# Atemgea_schematic.net
KiCad netlist of a schematic drawn in Altium Designer
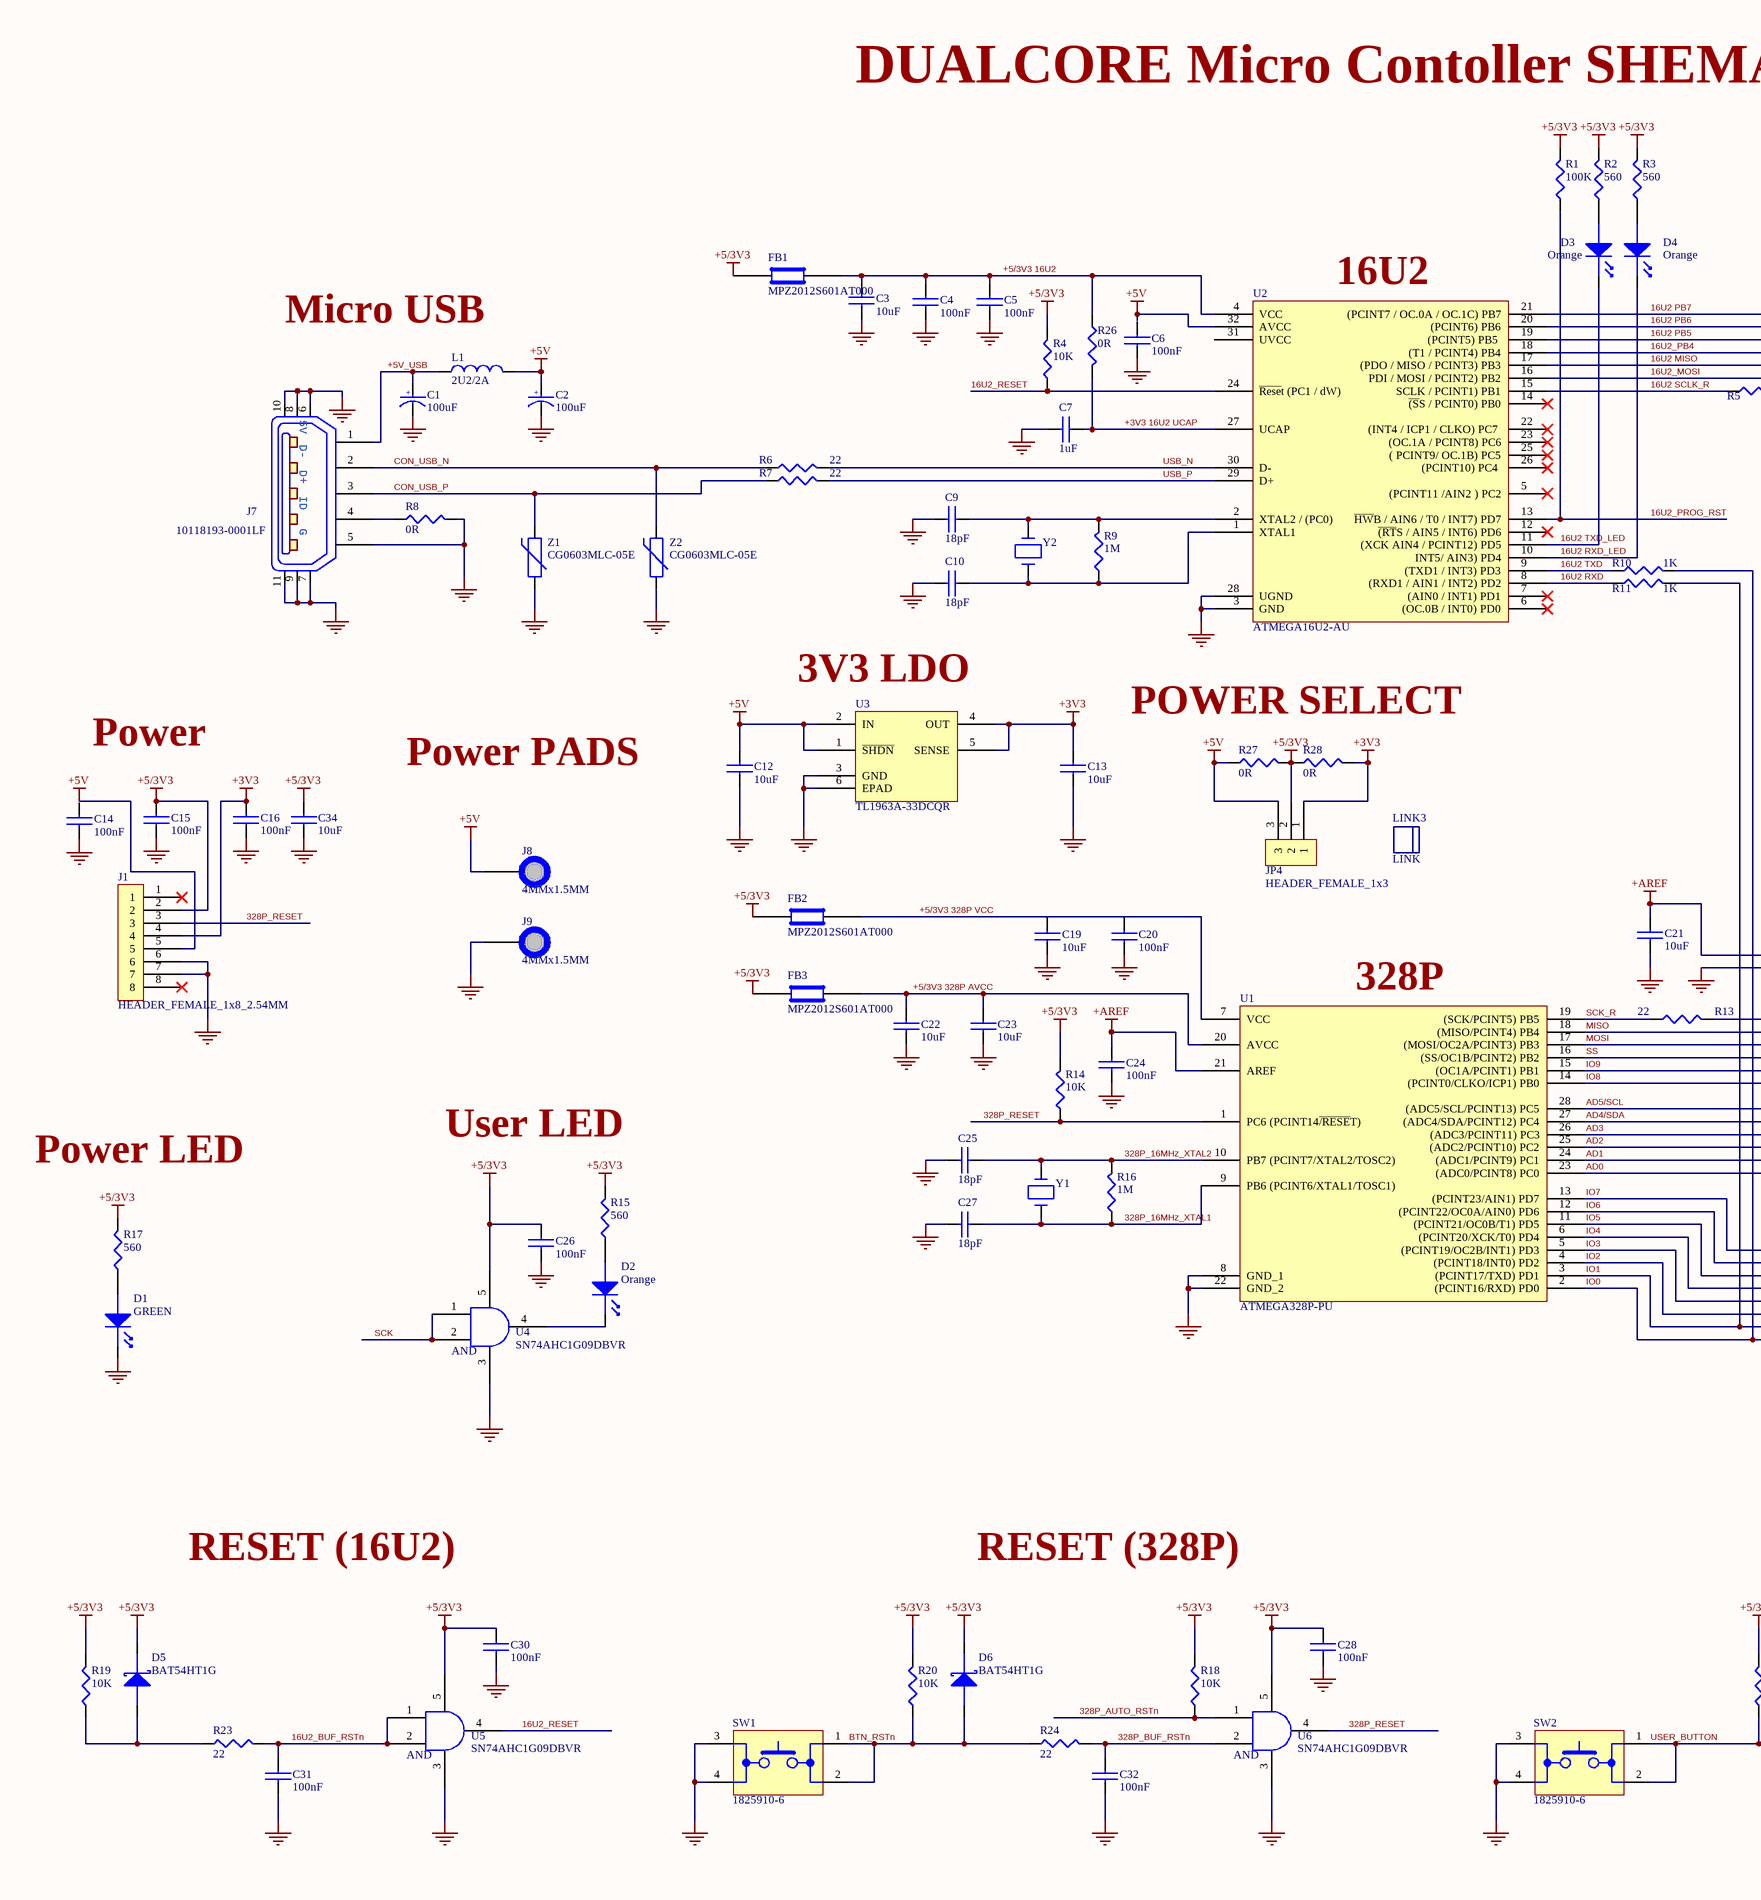
[diagram p0: Atemgea_schematic.SchDoc, left]
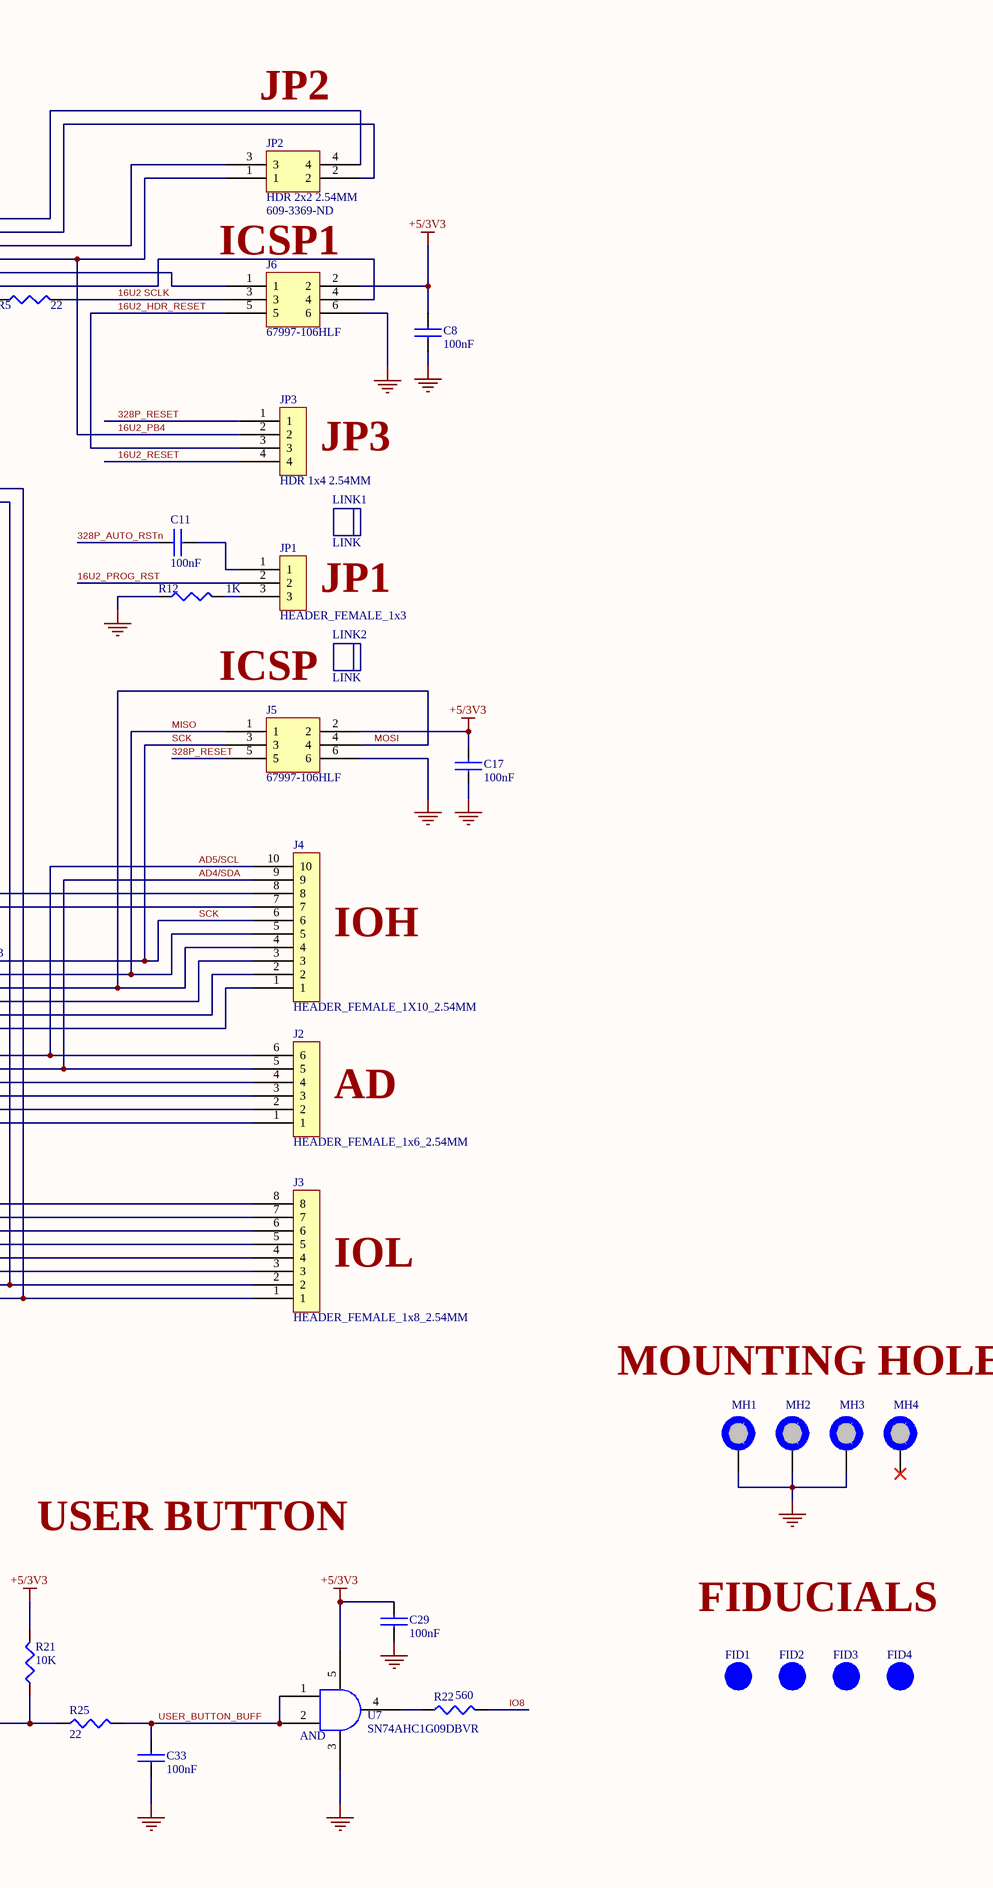
[diagram p1: Atemgea_schematic.SchDoc, right]

(export (version "E")
  (design (tool "Eeschema 10.0.6"))
  (components
    (comp (ref "C1")
      (value "100uF")
      (footprint "C_ALU_C_SIZE")
      (description "Cap Aluminum 100uF 10V 20% (5 X 5.4mm) SMD 50mA 1000 hr 85°C T/R")
      (fields
        (field (name "MANUFACTURER") "Panasonic")
        (field (name "MANUFACTURER PART NUMBER") "EEE-1AA101WR")
      )
      (libsource (lib "atmega_shlib") (part "EEE-1AA101WR"))
    )
    (comp (ref "C2")
      (value "100uF")
      (footprint "C_ALU_C_SIZE")
      (description "Cap Aluminum 100uF 10V 20% (5 X 5.4mm) SMD 50mA 1000 hr 85°C T/R")
      (fields
        (field (name "MANUFACTURER") "Panasonic")
        (field (name "MANUFACTURER PART NUMBER") "EEE-1AA101WR")
      )
      (libsource (lib "atmega_shlib") (part "EEE-1AA101WR"))
    )
    (comp (ref "C3")
      (value "10uF")
      (footprint "C0805")
      (description "Cap Ceramic 10uF 10V X7S 20% Pad SMD 0805 125°C Low ESR Automotive T/R")
      (fields
        (field (name "MANUFACTURER") "TDK")
        (field (name "MANUFACTURER PART NUMBER") "CGA4J3X7S1A106M125AB")
      )
      (libsource (lib "atmega_shlib") (part "CGA4J3X7S1A106M125AB"))
    )
    (comp (ref "C4")
      (value "100nF")
      (footprint "C0805")
      (description "Cap Ceramic 0.1uF 50V X7R 10% Pad SMD 0805 125°C Automotive T/R")
      (fields
        (field (name "MANUFACTURER") "TDK")
        (field (name "MANUFACTURER PART NUMBER") "CGA4J2X7R1H104K125AM")
      )
      (libsource (lib "atmega_shlib") (part "CGA4J2X7R1H104K125AM"))
    )
    (comp (ref "C5")
      (value "100nF")
      (footprint "C0805")
      (description "Cap Ceramic 0.1uF 50V X7R 10% Pad SMD 0805 125°C Automotive T/R")
      (fields
        (field (name "MANUFACTURER") "TDK")
        (field (name "MANUFACTURER PART NUMBER") "CGA4J2X7R1H104K125AM")
      )
      (libsource (lib "atmega_shlib") (part "CGA4J2X7R1H104K125AM"))
    )
    (comp (ref "C6")
      (value "100nF")
      (footprint "C0805")
      (description "Cap Ceramic 0.1uF 50V X7R 10% Pad SMD 0805 125°C Automotive T/R")
      (fields
        (field (name "MANUFACTURER") "TDK")
        (field (name "MANUFACTURER PART NUMBER") "CGA4J2X7R1H104K125AM")
      )
      (libsource (lib "atmega_shlib") (part "CGA4J2X7R1H104K125AM"))
    )
    (comp (ref "C7")
      (value "1uF")
      (footprint "C0805")
      (fields
        (field (name "MANUFACTURER") "TDK")
        (field (name "MANUFACTURER PART NUMBER") "C2012X5R1E105K125AA")
        (field (name "TOLERANCE") "10%")
      )
      (libsource (lib "atmega_shlib") (part "C2012X5R1E105K125AA"))
    )
    (comp (ref "C8")
      (value "100nF")
      (footprint "C0805")
      (description "Cap Ceramic 0.1uF 50V X7R 10% Pad SMD 0805 125°C Automotive T/R")
      (fields
        (field (name "MANUFACTURER") "TDK")
        (field (name "MANUFACTURER PART NUMBER") "CGA4J2X7R1H104K125AM")
      )
      (libsource (lib "atmega_shlib") (part "CGA4J2X7R1H104K125AM"))
    )
    (comp (ref "C9")
      (value "18pF")
      (footprint "C0805")
      (description "Cap Ceramic 18pF 50V C0G 5% SMD 0805 125C Paper T/R")
      (fields
        (field (name "MANUFACTURER") "KEMET")
        (field (name "MANUFACTURER PART NUMBER") "C0805C180J5GACTU")
      )
      (libsource (lib "atmega_shlib") (part "C0805C180J5GACTU"))
    )
    (comp (ref "C10")
      (value "18pF")
      (footprint "C0805")
      (description "Cap Ceramic 18pF 50V C0G 5% SMD 0805 125C Paper T/R")
      (fields
        (field (name "MANUFACTURER") "KEMET")
        (field (name "MANUFACTURER PART NUMBER") "C0805C180J5GACTU")
      )
      (libsource (lib "atmega_shlib") (part "C0805C180J5GACTU"))
    )
    (comp (ref "C11")
      (value "100nF")
      (footprint "C0805")
      (description "Cap Ceramic 0.1uF 50V X7R 10% Pad SMD 0805 125°C Automotive T/R")
      (fields
        (field (name "MANUFACTURER") "TDK")
        (field (name "MANUFACTURER PART NUMBER") "CGA4J2X7R1H104K125AM")
      )
      (libsource (lib "atmega_shlib") (part "CGA4J2X7R1H104K125AM"))
    )
    (comp (ref "C12")
      (value "10uF")
      (footprint "C0805")
      (description "Cap Ceramic 10uF 10V X7S 20% Pad SMD 0805 125°C Low ESR Automotive T/R")
      (fields
        (field (name "MANUFACTURER") "TDK")
        (field (name "MANUFACTURER PART NUMBER") "CGA4J3X7S1A106M125AB")
      )
      (libsource (lib "atmega_shlib") (part "CGA4J3X7S1A106M125AB"))
    )
    (comp (ref "C13")
      (value "10uF")
      (footprint "C0805")
      (description "Cap Ceramic 10uF 10V X7S 20% Pad SMD 0805 125°C Low ESR Automotive T/R")
      (fields
        (field (name "MANUFACTURER") "TDK")
        (field (name "MANUFACTURER PART NUMBER") "CGA4J3X7S1A106M125AB")
      )
      (libsource (lib "atmega_shlib") (part "CGA4J3X7S1A106M125AB"))
    )
    (comp (ref "C14")
      (value "100nF")
      (footprint "C0805")
      (description "Cap Ceramic 0.1uF 50V X7R 10% Pad SMD 0805 125°C Automotive T/R")
      (fields
        (field (name "MANUFACTURER") "TDK")
        (field (name "MANUFACTURER PART NUMBER") "CGA4J2X7R1H104K125AM")
      )
      (libsource (lib "atmega_shlib") (part "CGA4J2X7R1H104K125AM"))
    )
    (comp (ref "C15")
      (value "100nF")
      (footprint "C0805")
      (description "Cap Ceramic 0.1uF 50V X7R 10% Pad SMD 0805 125°C Automotive T/R")
      (fields
        (field (name "MANUFACTURER") "TDK")
        (field (name "MANUFACTURER PART NUMBER") "CGA4J2X7R1H104K125AM")
      )
      (libsource (lib "atmega_shlib") (part "CGA4J2X7R1H104K125AM"))
    )
    (comp (ref "C16")
      (value "100nF")
      (footprint "C0805")
      (description "Cap Ceramic 0.1uF 50V X7R 10% Pad SMD 0805 125°C Automotive T/R")
      (fields
        (field (name "MANUFACTURER") "TDK")
        (field (name "MANUFACTURER PART NUMBER") "CGA4J2X7R1H104K125AM")
      )
      (libsource (lib "atmega_shlib") (part "CGA4J2X7R1H104K125AM"))
    )
    (comp (ref "C17")
      (value "100nF")
      (footprint "C0805")
      (description "Cap Ceramic 0.1uF 50V X7R 10% Pad SMD 0805 125°C Automotive T/R")
      (fields
        (field (name "MANUFACTURER") "TDK")
        (field (name "MANUFACTURER PART NUMBER") "CGA4J2X7R1H104K125AM")
      )
      (libsource (lib "atmega_shlib") (part "CGA4J2X7R1H104K125AM"))
    )
    (comp (ref "C19")
      (value "10uF")
      (footprint "C0805")
      (description "Cap Ceramic 10uF 10V X7S 20% Pad SMD 0805 125°C Low ESR Automotive T/R")
      (fields
        (field (name "MANUFACTURER") "TDK")
        (field (name "MANUFACTURER PART NUMBER") "CGA4J3X7S1A106M125AB")
      )
      (libsource (lib "atmega_shlib") (part "CGA4J3X7S1A106M125AB"))
    )
    (comp (ref "C20")
      (value "100nF")
      (footprint "C0805")
      (description "Cap Ceramic 0.1uF 50V X7R 10% Pad SMD 0805 125°C Automotive T/R")
      (fields
        (field (name "MANUFACTURER") "TDK")
        (field (name "MANUFACTURER PART NUMBER") "CGA4J2X7R1H104K125AM")
      )
      (libsource (lib "atmega_shlib") (part "CGA4J2X7R1H104K125AM"))
    )
    (comp (ref "C21")
      (value "10uF")
      (footprint "C0805")
      (description "Cap Ceramic 10uF 10V X7S 20% Pad SMD 0805 125°C Low ESR Automotive T/R")
      (fields
        (field (name "MANUFACTURER") "TDK")
        (field (name "MANUFACTURER PART NUMBER") "CGA4J3X7S1A106M125AB")
      )
      (libsource (lib "atmega_shlib") (part "CGA4J3X7S1A106M125AB"))
    )
    (comp (ref "C22")
      (value "10uF")
      (footprint "C0805")
      (description "Cap Ceramic 10uF 10V X7S 20% Pad SMD 0805 125°C Low ESR Automotive T/R")
      (fields
        (field (name "MANUFACTURER") "TDK")
        (field (name "MANUFACTURER PART NUMBER") "CGA4J3X7S1A106M125AB")
      )
      (libsource (lib "atmega_shlib") (part "CGA4J3X7S1A106M125AB"))
    )
    (comp (ref "C23")
      (value "10uF")
      (footprint "C0805")
      (description "Cap Ceramic 10uF 10V X7S 20% Pad SMD 0805 125°C Low ESR Automotive T/R")
      (fields
        (field (name "MANUFACTURER") "TDK")
        (field (name "MANUFACTURER PART NUMBER") "CGA4J3X7S1A106M125AB")
      )
      (libsource (lib "atmega_shlib") (part "CGA4J3X7S1A106M125AB"))
    )
    (comp (ref "C24")
      (value "100nF")
      (footprint "C0805")
      (description "Cap Ceramic 0.1uF 50V X7R 10% Pad SMD 0805 125°C Automotive T/R")
      (fields
        (field (name "MANUFACTURER") "TDK")
        (field (name "MANUFACTURER PART NUMBER") "CGA4J2X7R1H104K125AM")
      )
      (libsource (lib "atmega_shlib") (part "CGA4J2X7R1H104K125AM"))
    )
    (comp (ref "C25")
      (value "18pF")
      (footprint "C0805")
      (description "Cap Ceramic 18pF 50V C0G 5% SMD 0805 125C Paper T/R")
      (fields
        (field (name "MANUFACTURER") "KEMET")
        (field (name "MANUFACTURER PART NUMBER") "C0805C180J5GACTU")
      )
      (libsource (lib "atmega_shlib") (part "C0805C180J5GACTU"))
    )
    (comp (ref "C26")
      (value "100nF")
      (footprint "C0805")
      (description "Cap Ceramic 0.1uF 50V X7R 10% Pad SMD 0805 125°C Automotive T/R")
      (fields
        (field (name "MANUFACTURER") "TDK")
        (field (name "MANUFACTURER PART NUMBER") "CGA4J2X7R1H104K125AM")
      )
      (libsource (lib "atmega_shlib") (part "CGA4J2X7R1H104K125AM"))
    )
    (comp (ref "C27")
      (value "18pF")
      (footprint "C0805")
      (description "Cap Ceramic 18pF 50V C0G 5% SMD 0805 125C Paper T/R")
      (fields
        (field (name "MANUFACTURER") "KEMET")
        (field (name "MANUFACTURER PART NUMBER") "C0805C180J5GACTU")
      )
      (libsource (lib "atmega_shlib") (part "C0805C180J5GACTU"))
    )
    (comp (ref "C28")
      (value "100nF")
      (footprint "C0805")
      (description "Cap Ceramic 0.1uF 50V X7R 10% Pad SMD 0805 125°C Automotive T/R")
      (fields
        (field (name "MANUFACTURER") "TDK")
        (field (name "MANUFACTURER PART NUMBER") "CGA4J2X7R1H104K125AM")
      )
      (libsource (lib "atmega_shlib") (part "CGA4J2X7R1H104K125AM"))
    )
    (comp (ref "C29")
      (value "100nF")
      (footprint "C0805")
      (description "Cap Ceramic 0.1uF 50V X7R 10% Pad SMD 0805 125°C Automotive T/R")
      (fields
        (field (name "MANUFACTURER") "TDK")
        (field (name "MANUFACTURER PART NUMBER") "CGA4J2X7R1H104K125AM")
      )
      (libsource (lib "atmega_shlib") (part "CGA4J2X7R1H104K125AM"))
    )
    (comp (ref "C30")
      (value "100nF")
      (footprint "C0805")
      (description "Cap Ceramic 0.1uF 50V X7R 10% Pad SMD 0805 125°C Automotive T/R")
      (fields
        (field (name "MANUFACTURER") "TDK")
        (field (name "MANUFACTURER PART NUMBER") "CGA4J2X7R1H104K125AM")
      )
      (libsource (lib "atmega_shlib") (part "CGA4J2X7R1H104K125AM"))
    )
    (comp (ref "C31")
      (value "100nF")
      (footprint "C0805")
      (description "Cap Ceramic 0.1uF 50V X7R 10% Pad SMD 0805 125°C Automotive T/R")
      (fields
        (field (name "MANUFACTURER") "TDK")
        (field (name "MANUFACTURER PART NUMBER") "CGA4J2X7R1H104K125AM")
      )
      (libsource (lib "atmega_shlib") (part "CGA4J2X7R1H104K125AM"))
    )
    (comp (ref "C32")
      (value "100nF")
      (footprint "C0805")
      (description "Cap Ceramic 0.1uF 50V X7R 10% Pad SMD 0805 125°C Automotive T/R")
      (fields
        (field (name "MANUFACTURER") "TDK")
        (field (name "MANUFACTURER PART NUMBER") "CGA4J2X7R1H104K125AM")
      )
      (libsource (lib "atmega_shlib") (part "CGA4J2X7R1H104K125AM"))
    )
    (comp (ref "C33")
      (value "100nF")
      (footprint "C0805")
      (description "Cap Ceramic 0.1uF 50V X7R 10% Pad SMD 0805 125°C Automotive T/R")
      (fields
        (field (name "MANUFACTURER") "TDK")
        (field (name "MANUFACTURER PART NUMBER") "CGA4J2X7R1H104K125AM")
      )
      (libsource (lib "atmega_shlib") (part "CGA4J2X7R1H104K125AM"))
    )
    (comp (ref "C34")
      (value "10uF")
      (footprint "C0805")
      (description "Cap Ceramic 10uF 10V X7S 20% Pad SMD 0805 125°C Low ESR Automotive T/R")
      (fields
        (field (name "MANUFACTURER") "TDK")
        (field (name "MANUFACTURER PART NUMBER") "CGA4J3X7S1A106M125AB")
      )
      (libsource (lib "atmega_shlib") (part "CGA4J3X7S1A106M125AB"))
    )
    (comp (ref "D1")
      (value "GREEN")
      (footprint "LED0603")
      (description "LED Single Chip Green 570nm 20mA 2-Pin 0603 T/R")
      (fields
        (field (name "MANUFACTURER") "Osram Opto")
        (field (name "MANUFACTURER PART NUMBER") "LGL29K-G2J1-24-Z")
      )
      (libsource (lib "atmega_shlib") (part "LGL29K-G2J1-24-Z"))
    )
    (comp (ref "D2")
      (value "Orange")
      (footprint "LED0603")
      (description "Smartled Orange Lc")
      (fields
        (field (name "MANUFACTURER") "Osram Opto")
        (field (name "MANUFACTURER PART NUMBER") "LOL29K-H2K1-24-Z")
      )
      (libsource (lib "atmega_shlib") (part "LOL29K-H2K1-24-Z"))
    )
    (comp (ref "D3")
      (value "Orange")
      (footprint "LED0603")
      (description "Smartled Orange Lc")
      (fields
        (field (name "MANUFACTURER") "Osram Opto")
        (field (name "MANUFACTURER PART NUMBER") "LOL29K-H2K1-24-Z")
      )
      (libsource (lib "atmega_shlib") (part "LOL29K-H2K1-24-Z"))
    )
    (comp (ref "D4")
      (value "Orange")
      (footprint "LED0603")
      (description "Smartled Orange Lc")
      (fields
        (field (name "MANUFACTURER") "Osram Opto")
        (field (name "MANUFACTURER PART NUMBER") "LOL29K-H2K1-24-Z")
      )
      (libsource (lib "atmega_shlib") (part "LOL29K-H2K1-24-Z"))
    )
    (comp (ref "D5")
      (value "BAT54HT1G")
      (footprint "SOD323")
      (description "Small Signal Schottky Diode, Single, 30 V, 200 Ma, 800 Mv, 600 Ma, 150 C")
      (fields (field (name "MANUFACTURER") "ON Semiconductor / Fairchild"))
      (libsource (lib "atmega_shlib") (part "BAT54HT1G"))
    )
    (comp (ref "D6")
      (value "BAT54HT1G")
      (footprint "SOD323")
      (description "Small Signal Schottky Diode, Single, 30 V, 200 Ma, 800 Mv, 600 Ma, 150 C")
      (fields (field (name "MANUFACTURER") "ON Semiconductor / Fairchild"))
      (libsource (lib "atmega_shlib") (part "BAT54HT1G"))
    )
    (comp (ref "FB1")
      (value "MPZ2012S601AT000")
      (footprint "C0805")
      (description "Ferrite Beads Multi-Layer Power 600Ohm 25% 100MHz 2A 100mOhm DCR 0805 T/R")
      (fields (field (name "MANUFACTURER") "TDK"))
      (libsource (lib "atmega_shlib") (part "MPZ2012S601AT000"))
    )
    (comp (ref "FB2")
      (value "MPZ2012S601AT000")
      (footprint "C0805")
      (description "Ferrite Beads Multi-Layer Power 600Ohm 25% 100MHz 2A 100mOhm DCR 0805 T/R")
      (fields (field (name "MANUFACTURER") "TDK"))
      (libsource (lib "atmega_shlib") (part "MPZ2012S601AT000"))
    )
    (comp (ref "FB3")
      (value "MPZ2012S601AT000")
      (footprint "C0805")
      (description "Ferrite Beads Multi-Layer Power 600Ohm 25% 100MHz 2A 100mOhm DCR 0805 T/R")
      (fields (field (name "MANUFACTURER") "TDK"))
      (libsource (lib "atmega_shlib") (part "MPZ2012S601AT000"))
    )
    (comp (ref "FID1")
      (value "FID_1MM")
      (footprint "FID_x_420")
      (description "Fisushal 1MM")
      (libsource (lib "atmega_shlib") (part "FID_1MM"))
    )
    (comp (ref "FID2")
      (value "FID_1MM")
      (footprint "FID_x_420")
      (description "Fisushal 1MM")
      (libsource (lib "atmega_shlib") (part "FID_1MM"))
    )
    (comp (ref "FID3")
      (value "FID_1MM")
      (footprint "FID_x_420")
      (description "Fisushal 1MM")
      (libsource (lib "atmega_shlib") (part "FID_1MM"))
    )
    (comp (ref "FID4")
      (value "FID_1MM")
      (footprint "FID_x_420")
      (description "Fisushal 1MM")
      (libsource (lib "atmega_shlib") (part "FID_1MM"))
    )
    (comp (ref "J1")
      (value "HEADER_FEMALE_1x8_2.54MM")
      (footprint "FEMALE_HEADER_1x8_2.54MM")
      (description "Female, 8C, Straight, .100\"CC; 3.20mm Tail, No Mt. 100u\" Tin; PBT, Phos Bronze, 105 C")
      (fields
        (field (name "MANUFACTURER") "Sullins")
        (field (name "MANUFACTURER PART NUMBER") "PPTC081LFBN-RC")
      )
      (libsource (lib "atmega_shlib") (part "PPTC081LFBN-RC"))
    )
    (comp (ref "J2")
      (value "HEADER_FEMALE_1x6_2.54MM")
      (footprint "FEMALE_HEADER_1x6_2.54MM")
      (description "2.54mm (0.1\") Pitch SIL Vertical PC Tail Socket Assembly, selective gold + tin, 6 contacts")
      (fields (field (name "MANUFACTURER") "Harwin") (field (name "MANUFACTURER PART NUMBER") "M20-7820642"))
      (libsource (lib "atmega_shlib") (part "M20-7820642"))
    )
    (comp (ref "J3")
      (value "HEADER_FEMALE_1x8_2.54MM")
      (footprint "FEMALE_HEADER_1x8_2.54MM")
      (description "Female, 8C, Straight, .100\"CC; 3.20mm Tail, No Mt. 100u\" Tin; PBT, Phos Bronze, 105 C")
      (fields
        (field (name "MANUFACTURER") "Sullins")
        (field (name "MANUFACTURER PART NUMBER") "PPTC081LFBN-RC")
      )
      (libsource (lib "") (part "PPTC081LFBN-RC_1"))
    )
    (comp (ref "J4")
      (value "HEADER_FEMALE_1X10_2.54MM")
      (footprint "FEMALE_HEADER_1x10_2.54MM")
      (description "2.54mm (0.1\") Pitch SIL Vertical PC Tail Socket Assembly, tin, 10 contacts")
      (fields (field (name "MANUFACTURER") "Harwin") (field (name "MANUFACTURER PART NUMBER") "M20-7821046"))
      (libsource (lib "atmega_shlib") (part "M20-7821046"))
    )
    (comp (ref "J5")
      (value "67997-106HLF")
      (footprint "HDR_2x3_2.54MM")
      (description "Conn Unshrouded Header HDR 6 POS 2.54mm Solder ST Top Entry Thru-Hole BergStik® Bulk")
      (fields (field (name "MANUFACTURER") "ICC"))
      (libsource (lib "atmega_shlib") (part "67997-106HLF"))
    )
    (comp (ref "J6")
      (value "67997-106HLF")
      (footprint "HDR_2x3_2.54MM")
      (description "Conn Unshrouded Header HDR 6 POS 2.54mm Solder ST Top Entry Thru-Hole BergStik® Bulk")
      (fields (field (name "MANUFACTURER") "ICC"))
      (libsource (lib "atmega_shlib") (part "67997-106HLF"))
    )
    (comp (ref "J7")
      (value "10118193-0001LF")
      (footprint "10118193-0001LF")
      (description "FCI Right Angle Surface Mount Mount Female USB Connector; 100 V ac; 1.8A")
      (fields (field (name "MANUFACTURER") "Amphenol ICC / FCI"))
      (libsource (lib "atmega_shlib") (part "10118193-0001LF"))
    )
    (comp (ref "J8")
      (value "4MMx1.5MM")
      (footprint "PAD_WITH_HOLE_4MM_1.5MM")
      (description "A pad with a hole of 1.5 mm. And the pad size 4mm")
      (libsource (lib "atmega_shlib") (part "PAD_HOLE_4MM-1.5MM"))
    )
    (comp (ref "J9")
      (value "4MMx1.5MM")
      (footprint "PAD_WITH_HOLE_4MM_1.5MM")
      (description "A pad with a hole of 1.5 mm. And the pad size 4mm")
      (libsource (lib "atmega_shlib") (part "PAD_HOLE_4MM-1.5MM"))
    )
    (comp (ref "JP1")
      (value "HEADER_FEMALE_1x3")
      (footprint "HDR_1x3_2.54MM")
      (description "Conn Unshrouded Header HDR 3 POS 2.54mm Solder ST Top Entry Thru-Hole BergStik® Automotive Bulk")
      (fields
        (field (name "MANUFACTURER") "Amphenol ICC")
        (field (name "MANUFACTURER PART NUMBER") "68000-103HLF")
      )
      (libsource (lib "atmega_shlib") (part "68000-103HLF"))
    )
    (comp (ref "JP2")
      (value "HDR 2x2 2.54MM")
      (footprint "HDR_2x2_2.54MM")
      (description "Conn Unshrouded Header HDR 4 POS 2.54mm Solder ST Top Entry Thru-Hole BergStik® Bulk")
      (fields
        (field (name "MANUFACTURER") "Amphenol ICC / FCI")
        (field (name "MANUFACTURER PART NUMBER") "68602-204HLF")
        (field (name "SUPPLIER PART NUMBER 1") "609-3369-ND")
      )
      (libsource (lib "atmega_shlib") (part "68602-204HLF"))
    )
    (comp (ref "JP3")
      (value "HDR 1x4 2.54MM")
      (footprint "MALEHEADER_1x4_2.54MM")
      (description "Conn Unshrouded Header HDR 4 POS 2.54mm Solder ST Thru-Hole Bag")
      (fields
        (field (name "MANUFACTURER") "Amphenol ICC / FCI")
        (field (name "MANUFACTURER PART NUMBER") "68001-204HLF")
      )
      (libsource (lib "atmega_shlib") (part "68001-204HLF"))
    )
    (comp (ref "JP4")
      (value "HEADER_FEMALE_1x3")
      (footprint "HDR_1x3_2.54MM")
      (description "Conn Unshrouded Header HDR 3 POS 2.54mm Solder ST Top Entry Thru-Hole BergStik® Automotive Bulk")
      (fields
        (field (name "MANUFACTURER") "Amphenol ICC")
        (field (name "MANUFACTURER PART NUMBER") "68000-103HLF")
      )
      (libsource (lib "") (part "68000-103HLF_1"))
    )
    (comp (ref "L1")
      (value "2U2/2A")
      (footprint "CL_inductor")
      (description "Inductor RF Chip Wirewound 2.2uH 20% 100KHz 1.13A 0.104Ohm DCR 1210 T/R")
      (fields
        (field (name "MANUFACTURER") "KEMET")
        (field (name "MANUFACTURER PART NUMBER") "L1210R2R2MDWIT")
      )
      (libsource (lib "atmega_shlib") (part "L1210R2R2MDWIT"))
    )
    (comp (ref "LINK1")
      (value "LINK")
      (description "2 Position 2.54 mm Centerline Single Circuit Open Top Jumper")
      (fields
        (field (name "MANUFACTURER") "Sullins")
        (field (name "MANUFACTURER PART NUMBER") "QPC02SXGN-RC")
      )
      (libsource (lib "atmega_shlib") (part "QPC02SXGN-RC"))
    )
    (comp (ref "LINK2")
      (value "LINK")
      (description "2 Position 2.54 mm Centerline Single Circuit Open Top Jumper")
      (fields
        (field (name "MANUFACTURER") "Sullins")
        (field (name "MANUFACTURER PART NUMBER") "QPC02SXGN-RC")
      )
      (libsource (lib "atmega_shlib") (part "QPC02SXGN-RC"))
    )
    (comp (ref "LINK3")
      (value "LINK")
      (description "2 Position 2.54 mm Centerline Single Circuit Open Top Jumper")
      (fields
        (field (name "MANUFACTURER") "Sullins")
        (field (name "MANUFACTURER PART NUMBER") "QPC02SXGN-RC")
      )
      (libsource (lib "atmega_shlib") (part "QPC02SXGN-RC"))
    )
    (comp (ref "MH1")
      (value "Mounting_hole_17.4_3.2")
      (footprint "MH_17.4_3.2")
      (description "Mounting Hole plated")
      (libsource (lib "atmega_shlib") (part "Mounting_hole_17.4_3.2"))
    )
    (comp (ref "MH2")
      (value "Mounting_hole_17.4_3.2")
      (footprint "MH_17.4_3.2")
      (description "Mounting Hole plated")
      (libsource (lib "atmega_shlib") (part "Mounting_hole_17.4_3.2"))
    )
    (comp (ref "MH3")
      (value "Mounting_hole_17.4_3.2")
      (footprint "MH_17.4_3.2")
      (description "Mounting Hole plated")
      (libsource (lib "atmega_shlib") (part "Mounting_hole_17.4_3.2"))
    )
    (comp (ref "MH4")
      (value "Mounting_hole_17.4_3.2")
      (footprint "MH_17.4_3.2")
      (description "Mounting Hole plated")
      (libsource (lib "atmega_shlib") (part "Mounting_hole_17.4_3.2"))
    )
    (comp (ref "R1")
      (value "100K")
      (footprint "R0805")
      (description "Res Thick Film 0805 100K Ohm 1% 1/8W ±100ppm/°C Molded SMD Paper T/R")
      (fields
        (field (name "MANUFACTURER") "Yageo")
        (field (name "MANUFACTURER PART NUMBER") "RC0805FR-07100KL")
      )
      (libsource (lib "atmega_shlib") (part "RC0805FR-07100KL"))
    )
    (comp (ref "R2")
      (value "560")
      (footprint "R0805")
      (description "Res General Purpose Thick Film 0805 560 Ohm 1% 1/8W ±100ppm/°C Molded Paper T/R")
      (fields
        (field (name "MANUFACTURER") "Yageo")
        (field (name "MANUFACTURER PART NUMBER") "RC0805FR-07560RL")
      )
      (libsource (lib "atmega_shlib") (part "RC0805FR-07560RL"))
    )
    (comp (ref "R3")
      (value "560")
      (footprint "R0805")
      (description "Res General Purpose Thick Film 0805 560 Ohm 1% 1/8W ±100ppm/°C Molded Paper T/R")
      (fields
        (field (name "MANUFACTURER") "Yageo")
        (field (name "MANUFACTURER PART NUMBER") "RC0805FR-07560RL")
      )
      (libsource (lib "atmega_shlib") (part "RC0805FR-07560RL"))
    )
    (comp (ref "R4")
      (value "10K")
      (footprint "R0805")
      (description "Res SMD 0805 10K 1% 0.125W T.C.100PPM")
      (fields
        (field (name "MANUFACTURER") "Yageo")
        (field (name "MANUFACTURER PART NUMBER") "RC0805FR-0710KL")
      )
      (libsource (lib "atmega_shlib") (part "RC0805FR-0710KL"))
    )
    (comp (ref "R5")
      (value "22")
      (footprint "R0805")
      (description "Res SMD 0805 22R 1% 0.125W T.C.100PPM")
      (fields
        (field (name "MANUFACTURER") "Yageo")
        (field (name "MANUFACTURER PART NUMBER") "RC0805FR-0722RL")
      )
      (libsource (lib "atmega_shlib") (part "RC0805FR-0722RL"))
    )
    (comp (ref "R6")
      (value "22")
      (footprint "R0805")
      (description "Res SMD 0805 22R 1% 0.125W T.C.100PPM")
      (fields
        (field (name "MANUFACTURER") "Yageo")
        (field (name "MANUFACTURER PART NUMBER") "RC0805FR-0722RL")
      )
      (libsource (lib "atmega_shlib") (part "RC0805FR-0722RL"))
    )
    (comp (ref "R7")
      (value "22")
      (footprint "R0805")
      (description "Res SMD 0805 22R 1% 0.125W T.C.100PPM")
      (fields
        (field (name "MANUFACTURER") "Yageo")
        (field (name "MANUFACTURER PART NUMBER") "RC0805FR-0722RL")
      )
      (libsource (lib "atmega_shlib") (part "RC0805FR-0722RL"))
    )
    (comp (ref "R8")
      (value "0R")
      (footprint "R0805")
      (description "RC Series 0805 0.125 W 0 Ohm Jumper Surface Mount Thick Film Chip Resistor")
      (fields
        (field (name "MANUFACTURER") "Yageo")
        (field (name "MANUFACTURER PART NUMBER") "RC0805JR-070RL")
      )
      (libsource (lib "atmega_shlib") (part "RC0805JR-070RL"))
    )
    (comp (ref "R9")
      (value "1M")
      (footprint "R0805")
      (description "Res Thick Film 0805 1M Ohm 1% 0.125W(1/8W) ±100ppm/C Pad SMD T/R")
      (fields
        (field (name "MANUFACTURER") "Yageo Phycomp")
        (field (name "MANUFACTURER PART NUMBER") "RC0805FR-071ML")
      )
      (libsource (lib "atmega_shlib") (part "RC0805FR-071ML"))
    )
    (comp (ref "R10")
      (value "1K")
      (footprint "R0805")
      (description "Res Thick Film 0805 1KOhm 1% 0.125W(1/8W) 100ppm/C Epoxy Pad SMD T/R")
      (fields
        (field (name "MANUFACTURER") "Yageo")
        (field (name "MANUFACTURER PART NUMBER") "RC0805FR-071KL")
      )
      (libsource (lib "atmega_shlib") (part "RC0805FR-071KL"))
    )
    (comp (ref "R11")
      (value "1K")
      (footprint "R0805")
      (description "Res Thick Film 0805 1KOhm 1% 0.125W(1/8W) 100ppm/C Epoxy Pad SMD T/R")
      (fields
        (field (name "MANUFACTURER") "Yageo")
        (field (name "MANUFACTURER PART NUMBER") "RC0805FR-071KL")
      )
      (libsource (lib "atmega_shlib") (part "RC0805FR-071KL"))
    )
    (comp (ref "R12")
      (value "1K")
      (footprint "R0805")
      (description "Res Thick Film 0805 1KOhm 1% 0.125W(1/8W) 100ppm/C Epoxy Pad SMD T/R")
      (fields
        (field (name "MANUFACTURER") "Yageo")
        (field (name "MANUFACTURER PART NUMBER") "RC0805FR-071KL")
      )
      (libsource (lib "atmega_shlib") (part "RC0805FR-071KL"))
    )
    (comp (ref "R13")
      (value "22")
      (footprint "R0805")
      (description "Res SMD 0805 22R 1% 0.125W T.C.100PPM")
      (fields
        (field (name "MANUFACTURER") "Yageo")
        (field (name "MANUFACTURER PART NUMBER") "RC0805FR-0722RL")
      )
      (libsource (lib "atmega_shlib") (part "RC0805FR-0722RL"))
    )
    (comp (ref "R14")
      (value "10K")
      (footprint "R0805")
      (description "Res SMD 0805 10K 1% 0.125W T.C.100PPM")
      (fields
        (field (name "MANUFACTURER") "Yageo")
        (field (name "MANUFACTURER PART NUMBER") "RC0805FR-0710KL")
      )
      (libsource (lib "atmega_shlib") (part "RC0805FR-0710KL"))
    )
    (comp (ref "R15")
      (value "560")
      (footprint "R0805")
      (description "Res General Purpose Thick Film 0805 560 Ohm 1% 1/8W ±100ppm/°C Molded Paper T/R")
      (fields
        (field (name "MANUFACTURER") "Yageo")
        (field (name "MANUFACTURER PART NUMBER") "RC0805FR-07560RL")
      )
      (libsource (lib "atmega_shlib") (part "RC0805FR-07560RL"))
    )
    (comp (ref "R16")
      (value "1M")
      (footprint "R0805")
      (description "Res Thick Film 0805 1M Ohm 1% 0.125W(1/8W) ±100ppm/C Pad SMD T/R")
      (fields
        (field (name "MANUFACTURER") "Yageo Phycomp")
        (field (name "MANUFACTURER PART NUMBER") "RC0805FR-071ML")
      )
      (libsource (lib "atmega_shlib") (part "RC0805FR-071ML"))
    )
    (comp (ref "R17")
      (value "560")
      (footprint "R0805")
      (description "Res General Purpose Thick Film 0805 560 Ohm 1% 1/8W ±100ppm/°C Molded Paper T/R")
      (fields
        (field (name "MANUFACTURER") "Yageo")
        (field (name "MANUFACTURER PART NUMBER") "RC0805FR-07560RL")
      )
      (libsource (lib "atmega_shlib") (part "RC0805FR-07560RL"))
    )
    (comp (ref "R18")
      (value "10K")
      (footprint "R0805")
      (description "Res SMD 0805 10K 1% 0.125W T.C.100PPM")
      (fields
        (field (name "MANUFACTURER") "Yageo")
        (field (name "MANUFACTURER PART NUMBER") "RC0805FR-0710KL")
      )
      (libsource (lib "atmega_shlib") (part "RC0805FR-0710KL"))
    )
    (comp (ref "R19")
      (value "10K")
      (footprint "R0805")
      (description "Res SMD 0805 10K 1% 0.125W T.C.100PPM")
      (fields
        (field (name "MANUFACTURER") "Yageo")
        (field (name "MANUFACTURER PART NUMBER") "RC0805FR-0710KL")
      )
      (libsource (lib "atmega_shlib") (part "RC0805FR-0710KL"))
    )
    (comp (ref "R20")
      (value "10K")
      (footprint "R0805")
      (description "Res SMD 0805 10K 1% 0.125W T.C.100PPM")
      (fields
        (field (name "MANUFACTURER") "Yageo")
        (field (name "MANUFACTURER PART NUMBER") "RC0805FR-0710KL")
      )
      (libsource (lib "atmega_shlib") (part "RC0805FR-0710KL"))
    )
    (comp (ref "R21")
      (value "10K")
      (footprint "R0805")
      (description "Res SMD 0805 10K 1% 0.125W T.C.100PPM")
      (fields
        (field (name "MANUFACTURER") "Yageo")
        (field (name "MANUFACTURER PART NUMBER") "RC0805FR-0710KL")
      )
      (libsource (lib "atmega_shlib") (part "RC0805FR-0710KL"))
    )
    (comp (ref "R22")
      (value "560")
      (footprint "R0805")
      (description "Res General Purpose Thick Film 0805 560 Ohm 1% 1/8W ±100ppm/°C Molded Paper T/R")
      (fields
        (field (name "MANUFACTURER") "Yageo")
        (field (name "MANUFACTURER PART NUMBER") "RC0805FR-07560RL")
      )
      (libsource (lib "atmega_shlib") (part "RC0805FR-07560RL"))
    )
    (comp (ref "R23")
      (value "22")
      (footprint "R0805")
      (description "Res SMD 0805 22R 1% 0.125W T.C.100PPM")
      (fields
        (field (name "MANUFACTURER") "Yageo")
        (field (name "MANUFACTURER PART NUMBER") "RC0805FR-0722RL")
      )
      (libsource (lib "atmega_shlib") (part "RC0805FR-0722RL"))
    )
    (comp (ref "R24")
      (value "22")
      (footprint "R0805")
      (description "Res SMD 0805 22R 1% 0.125W T.C.100PPM")
      (fields
        (field (name "MANUFACTURER") "Yageo")
        (field (name "MANUFACTURER PART NUMBER") "RC0805FR-0722RL")
      )
      (libsource (lib "atmega_shlib") (part "RC0805FR-0722RL"))
    )
    (comp (ref "R25")
      (value "22")
      (footprint "R0805")
      (description "Res SMD 0805 22R 1% 0.125W T.C.100PPM")
      (fields
        (field (name "MANUFACTURER") "Yageo")
        (field (name "MANUFACTURER PART NUMBER") "RC0805FR-0722RL")
      )
      (libsource (lib "atmega_shlib") (part "RC0805FR-0722RL"))
    )
    (comp (ref "R26")
      (value "0R")
      (footprint "R0805")
      (description "RC Series 0805 0.125 W 0 Ohm Jumper Surface Mount Thick Film Chip Resistor")
      (fields
        (field (name "MANUFACTURER") "Yageo")
        (field (name "MANUFACTURER PART NUMBER") "RC0805JR-070RL")
      )
      (libsource (lib "atmega_shlib") (part "RC0805JR-070RL"))
    )
    (comp (ref "R27")
      (value "0R")
      (footprint "R0805")
      (description "RC Series 0805 0.125 W 0 Ohm Jumper Surface Mount Thick Film Chip Resistor")
      (fields
        (field (name "MANUFACTURER") "Yageo")
        (field (name "MANUFACTURER PART NUMBER") "RC0805JR-070RL")
      )
      (libsource (lib "atmega_shlib") (part "RC0805JR-070RL"))
    )
    (comp (ref "R28")
      (value "0R")
      (footprint "R0805")
      (description "RC Series 0805 0.125 W 0 Ohm Jumper Surface Mount Thick Film Chip Resistor")
      (fields
        (field (name "MANUFACTURER") "Yageo")
        (field (name "MANUFACTURER PART NUMBER") "RC0805JR-070RL")
      )
      (libsource (lib "atmega_shlib") (part "RC0805JR-070RL"))
    )
    (comp (ref "SW1")
      (value "1825910-6")
      (footprint "DIP41825910-6")
      (description "Switch Tactile OFF (ON) SPST Round Button PC Pins 0.05A 24VDC 1.57N Thru-Hole Loose")
      (fields (field (name "MANUFACTURER") "TE Connectivity Alcoswitch"))
      (libsource (lib "atmega_shlib") (part "1825910-6"))
    )
    (comp (ref "SW2")
      (value "1825910-6")
      (footprint "DIP41825910-6")
      (description "Switch Tactile OFF (ON) SPST Round Button PC Pins 0.05A 24VDC 1.57N Thru-Hole Loose")
      (fields (field (name "MANUFACTURER") "TE Connectivity Alcoswitch"))
      (libsource (lib "atmega_shlib") (part "1825910-6"))
    )
    (comp (ref "U1")
      (value "ATMEGA328P-PU")
      (footprint "DIP28_7.62mm")
      (description "ATMEGA328P-PU; 8 bit Microcontroller AVR 20MHz 1; 32kb Flash; 2kb RAM; I2C SPI 2")
      (fields (field (name "MANUFACTURER") "Microchip / Atmel"))
      (libsource (lib "atmega_shlib") (part "ATMEGA328P-PU"))
    )
    (comp (ref "U2")
      (value "ATMEGA16U2-AU")
      (footprint "TQFP_32")
      (description "8-bit AVR MCU, 16 KB, 512 Bytes, 16 MHz, 2.7 to 5.5V, TQFP-32, RoHS")
      (fields (field (name "MANUFACTURER") "Microchip / Atmel"))
      (libsource (lib "atmega_shlib") (part "ATMEGA16U2-AU"))
    )
    (comp (ref "U3")
      (value "TL1963A-33DCQR")
      (footprint "TL1963A-33DCQR")
      (description "LDO Regulator Pos 3.3V 1.5A 6-Pin(5+Tab) SOT-223 T/R")
      (fields (field (name "MANUFACTURER") "Texas Instruments"))
      (libsource (lib "atmega_shlib") (part "TL1963A-33DCQR"))
    )
    (comp (ref "U4")
      (value "SN74AHC1G09DBVR")
      (footprint "DBV_SOT_5")
      (description "Single 2-input, 2-V to 5.5-V AND gate with open-drain outputs 5-SOT-23 -55 to 125")
      (fields (field (name "MANUFACTURER") "Texas Instruments"))
      (libsource (lib "atmega_shlib") (part "SN74AHC1G09DBVR"))
    )
    (comp (ref "U5")
      (value "SN74AHC1G09DBVR")
      (footprint "DBV_SOT_5")
      (description "Single 2-input, 2-V to 5.5-V AND gate with open-drain outputs 5-SOT-23 -55 to 125")
      (fields (field (name "MANUFACTURER") "Texas Instruments"))
      (libsource (lib "atmega_shlib") (part "SN74AHC1G09DBVR"))
    )
    (comp (ref "U6")
      (value "SN74AHC1G09DBVR")
      (footprint "DBV_SOT_5")
      (description "Single 2-input, 2-V to 5.5-V AND gate with open-drain outputs 5-SOT-23 -55 to 125")
      (fields (field (name "MANUFACTURER") "Texas Instruments"))
      (libsource (lib "atmega_shlib") (part "SN74AHC1G09DBVR"))
    )
    (comp (ref "U7")
      (value "SN74AHC1G09DBVR")
      (footprint "DBV_SOT_5")
      (description "Single 2-input, 2-V to 5.5-V AND gate with open-drain outputs 5-SOT-23 -55 to 125")
      (fields (field (name "MANUFACTURER") "Texas Instruments"))
      (libsource (lib "atmega_shlib") (part "SN74AHC1G09DBVR"))
    )
    (comp (ref "Y1")
      (value "ABM7-16.000MHZ-D2Y-T")
      (footprint "ABM4_v1_1_BIG")
      (description "Crystal 16MHz ±20ppm (Tol) ±30ppm (Stability) 18pF FUND 50Ohm 2-Pin Mini-CSMD T/R")
      (fields (field (name "MANUFACTURER") "Abracon") (field (name "TOLERANCE") "20ppm"))
      (libsource (lib "atmega_shlib") (part "ABM7-16.000MHZ-D2Y-T"))
    )
    (comp (ref "Y2")
      (value "ABM7-16.000MHZ-D2Y-T")
      (footprint "ABM4_v1_1_BIG")
      (description "Crystal 16MHz ±20ppm (Tol) ±30ppm (Stability) 18pF FUND 50Ohm 2-Pin Mini-CSMD T/R")
      (fields (field (name "MANUFACTURER") "Abracon") (field (name "TOLERANCE") "20ppm"))
      (libsource (lib "atmega_shlib") (part "ABM7-16.000MHZ-D2Y-T"))
    )
    (comp (ref "Z1")
      (value "CG0603MLC-05E")
      (footprint "R0603")
      (description "ESD Suppressor Multilayer Varistor 5V Automotive 2-Pin Case 0603(1608Metric) T/R")
      (fields (field (name "MANUFACTURER") "Bourns") (field (name "VOLTAGE") "5V"))
      (libsource (lib "atmega_shlib") (part "CG0603MLC-05E"))
    )
    (comp (ref "Z2")
      (value "CG0603MLC-05E")
      (footprint "R0603")
      (description "ESD Suppressor Multilayer Varistor 5V Automotive 2-Pin Case 0603(1608Metric) T/R")
      (fields (field (name "MANUFACTURER") "Bourns") (field (name "VOLTAGE") "5V"))
      (libsource (lib "atmega_shlib") (part "CG0603MLC-05E"))
    )
  )
  (nets
    (net (code "1") (name "+3V3") (class "Default")
      (node (ref "C13") (pin "2") (pinfunction "2_2") (pintype "passive"))
      (node (ref "C16") (pin "2") (pinfunction "2_2") (pintype "passive"))
      (node (ref "J1") (pin "4") (pinfunction "4_4") (pintype "passive"))
      (node (ref "JP4") (pin "1") (pinfunction "1_1") (pintype "passive"))
      (node (ref "R28") (pin "2") (pinfunction "2_2") (pintype "passive"))
      (node (ref "U3") (pin "4") (pinfunction "OUT_4") (pintype "passive"))
      (node (ref "U3") (pin "5") (pinfunction "SENSE_5") (pintype "passive"))
    )
    (net (code "2") (name "+5V") (class "Default")
      (node (ref "C12") (pin "2") (pinfunction "2_2") (pintype "passive"))
      (node (ref "C2") (pin "1") (pinfunction "1_1") (pintype "passive"))
      (node (ref "J1") (pin "5") (pinfunction "5_5") (pintype "passive"))
      (node (ref "J8") (pin "1") (pinfunction "1_1") (pintype "passive"))
      (node (ref "JP4") (pin "3") (pinfunction "3_3") (pintype "passive"))
      (node (ref "L1") (pin "2") (pinfunction "2_2") (pintype "passive"))
      (node (ref "R27") (pin "1") (pinfunction "1_1") (pintype "passive"))
      (node (ref "U2") (pin "32") (pinfunction "AVCC_32") (pintype "passive"))
      (node (ref "U3") (pin "1") (pinfunction "~{SHDN}_1") (pintype "passive"))
      (node (ref "U3") (pin "2") (pinfunction "IN_2") (pintype "passive"))
    )
    (net (code "3") (name "+5{slash}3V3") (class "Default")
      (node (ref "C15") (pin "2") (pinfunction "2_2") (pintype "passive"))
      (node (ref "C17") (pin "2") (pinfunction "2_2") (pintype "passive"))
      (node (ref "C26") (pin "2") (pinfunction "2_2") (pintype "passive"))
      (node (ref "C28") (pin "2") (pinfunction "2_2") (pintype "passive"))
      (node (ref "C29") (pin "2") (pinfunction "2_2") (pintype "passive"))
      (node (ref "C30") (pin "2") (pinfunction "2_2") (pintype "passive"))
      (node (ref "C34") (pin "2") (pinfunction "2_2") (pintype "passive"))
      (node (ref "C8") (pin "2") (pinfunction "2_2") (pintype "passive"))
      (node (ref "D5") (pin "1") (pinfunction "Ca_1") (pintype "passive"))
      (node (ref "D6") (pin "1") (pinfunction "Ca_1") (pintype "passive"))
      (node (ref "FB1") (pin "1") (pinfunction "1_1") (pintype "passive"))
      (node (ref "FB2") (pin "1") (pinfunction "1_1") (pintype "passive"))
      (node (ref "FB3") (pin "1") (pinfunction "1_1") (pintype "passive"))
      (node (ref "J1") (pin "2") (pinfunction "2_2") (pintype "passive"))
      (node (ref "J5") (pin "2") (pinfunction "2_2") (pintype "passive"))
      (node (ref "J6") (pin "2") (pinfunction "2_2") (pintype "passive"))
      (node (ref "JP4") (pin "2") (pinfunction "2_2") (pintype "passive"))
      (node (ref "R1") (pin "2") (pinfunction "2_2") (pintype "passive"))
      (node (ref "R14") (pin "2") (pinfunction "2_2") (pintype "passive"))
      (node (ref "R15") (pin "2") (pinfunction "2_2") (pintype "passive"))
      (node (ref "R17") (pin "2") (pinfunction "2_2") (pintype "passive"))
      (node (ref "R18") (pin "2") (pinfunction "2_2") (pintype "passive"))
      (node (ref "R19") (pin "2") (pinfunction "2_2") (pintype "passive"))
      (node (ref "R2") (pin "2") (pinfunction "2_2") (pintype "passive"))
      (node (ref "R20") (pin "2") (pinfunction "2_2") (pintype "passive"))
      (node (ref "R21") (pin "2") (pinfunction "2_2") (pintype "passive"))
      (node (ref "R27") (pin "2") (pinfunction "2_2") (pintype "passive"))
      (node (ref "R28") (pin "1") (pinfunction "1_1") (pintype "passive"))
      (node (ref "R3") (pin "2") (pinfunction "2_2") (pintype "passive"))
      (node (ref "R4") (pin "2") (pinfunction "2_2") (pintype "passive"))
      (node (ref "U4") (pin "5") (pinfunction "5_5") (pintype "passive"))
      (node (ref "U5") (pin "5") (pinfunction "5_5") (pintype "passive"))
      (node (ref "U6") (pin "5") (pinfunction "5_5") (pintype "passive"))
      (node (ref "U7") (pin "5") (pinfunction "5_5") (pintype "passive"))
    )
    (net (code "4") (name "+AREF") (class "Default")
      (node (ref "C21") (pin "2") (pinfunction "2_2") (pintype "passive"))
      (node (ref "C24") (pin "2") (pinfunction "2_2") (pintype "passive"))
      (node (ref "J4") (pin "8") (pinfunction "8_8") (pintype "passive"))
      (node (ref "U1") (pin "21") (pinfunction "AREF_21") (pintype "passive"))
    )
    (net (code "5") (name "/+3V3 16U2 UCAP") (class "Default")
      (node (ref "C7") (pin "2") (pinfunction "2_2") (pintype "passive"))
      (node (ref "R26") (pin "2") (pinfunction "2_2") (pintype "passive"))
      (node (ref "U2") (pin "27") (pinfunction "UCAP_27") (pintype "passive"))
    )
    (net (code "6") (name "/+5V_USB") (class "Default")
      (node (ref "C1") (pin "1") (pinfunction "1_1") (pintype "passive"))
      (node (ref "J7") (pin "1") (pinfunction "1_1") (pintype "passive"))
      (node (ref "L1") (pin "1") (pinfunction "1_1") (pintype "passive"))
    )
    (net (code "7") (name "/+5{slash}3V3 16U2") (class "Default")
      (node (ref "C3") (pin "2") (pinfunction "2_2") (pintype "passive"))
      (node (ref "C4") (pin "2") (pinfunction "2_2") (pintype "passive"))
      (node (ref "C5") (pin "2") (pinfunction "2_2") (pintype "passive"))
      (node (ref "FB1") (pin "2") (pinfunction "2_2") (pintype "passive"))
      (node (ref "R26") (pin "1") (pinfunction "1_1") (pintype "passive"))
      (node (ref "U2") (pin "4") (pinfunction "VCC_4") (pintype "passive"))
    )
    (net (code "8") (name "/+5{slash}3V3 328P AVCC") (class "Default")
      (node (ref "C22") (pin "2") (pinfunction "2_2") (pintype "passive"))
      (node (ref "C23") (pin "2") (pinfunction "2_2") (pintype "passive"))
      (node (ref "FB3") (pin "2") (pinfunction "2_2") (pintype "passive"))
      (node (ref "U1") (pin "20") (pinfunction "AVCC_20") (pintype "passive"))
    )
    (net (code "9") (name "/+5{slash}3V3 328P VCC") (class "Default")
      (node (ref "FB2") (pin "2") (pinfunction "2_2") (pintype "passive"))
      (node (ref "U1") (pin "7") (pinfunction "VCC_7") (pintype "passive"))
    )
    (net (code "10") (name "/16U2 MISO") (class "Default")
      (node (ref "J6") (pin "1") (pinfunction "1_1") (pintype "passive"))
      (node (ref "U2") (pin "17") (pinfunction "(PDO_/_MISO_/_PCINT3)_PB3_17") (pintype "passive"))
    )
    (net (code "11") (name "/16U2 PB5") (class "Default")
      (node (ref "JP2") (pin "3") (pinfunction "3_3") (pintype "passive"))
      (node (ref "U2") (pin "19") (pinfunction "(PCINT5)_PB5_19") (pintype "passive"))
    )
    (net (code "12") (name "/16U2 PB6") (class "Default")
      (node (ref "JP2") (pin "2") (pinfunction "2_2") (pintype "passive"))
      (node (ref "U2") (pin "20") (pinfunction "(PCINT6)_PB6_20") (pintype "passive"))
    )
    (net (code "13") (name "/16U2 PB7") (class "Default")
      (node (ref "JP2") (pin "4") (pinfunction "4_4") (pintype "passive"))
      (node (ref "U2") (pin "21") (pinfunction "(PCINT7_/_OC.0A_/_OC.1C)_PB7_21") (pintype "passive"))
    )
    (net (code "14") (name "/16U2 RXD") (class "Default")
      (node (ref "R11") (pin "1") (pinfunction "1_1") (pintype "passive"))
      (node (ref "U2") (pin "8") (pinfunction "(RXD1_/_AIN1_/_INT2)_PD2_8") (pintype "passive"))
    )
    (net (code "15") (name "/16U2 RXD_LED") (class "Default")
      (node (ref "D4") (pin "1") (pinfunction "Ca_1") (pintype "passive"))
      (node (ref "U2") (pin "10") (pinfunction "INT5/_AIN3)_PD4_10") (pintype "passive"))
    )
    (net (code "16") (name "/16U2 SCLK") (class "Default")
      (node (ref "J6") (pin "3") (pinfunction "3_3") (pintype "passive"))
      (node (ref "R5") (pin "2") (pinfunction "2_2") (pintype "passive"))
    )
    (net (code "17") (name "/16U2 SCLK_R") (class "Default")
      (node (ref "R5") (pin "1") (pinfunction "1_1") (pintype "passive"))
      (node (ref "U2") (pin "15") (pinfunction "SCLK_/_PCINT1)_PB1_15") (pintype "passive"))
    )
    (net (code "18") (name "/16U2 TXD") (class "Default")
      (node (ref "R10") (pin "1") (pinfunction "1_1") (pintype "passive"))
      (node (ref "U2") (pin "9") (pinfunction "(TXD1_/_INT3)_PD3_9") (pintype "passive"))
    )
    (net (code "19") (name "/16U2 TXD_LED") (class "Default")
      (node (ref "D3") (pin "1") (pinfunction "Ca_1") (pintype "passive"))
      (node (ref "U2") (pin "11") (pinfunction "(XCK_AIN4_/_PCINT12)_PD5_11") (pintype "passive"))
    )
    (net (code "20") (name "/16U2_BUF_RSTn") (class "Default")
      (node (ref "C31") (pin "2") (pinfunction "2_2") (pintype "passive"))
      (node (ref "R23") (pin "2") (pinfunction "2_2") (pintype "passive"))
      (node (ref "U5") (pin "1") (pinfunction "1_1") (pintype "passive"))
      (node (ref "U5") (pin "2") (pinfunction "2_2") (pintype "passive"))
    )
    (net (code "21") (name "/16U2_HDR_RESET") (class "Default")
      (node (ref "J6") (pin "5") (pinfunction "5_5") (pintype "passive"))
      (node (ref "JP3") (pin "3") (pinfunction "3_3") (pintype "passive"))
    )
    (net (code "22") (name "/16U2_MOSI") (class "Default")
      (node (ref "J6") (pin "4") (pinfunction "4_4") (pintype "passive"))
      (node (ref "U2") (pin "16") (pinfunction "PDI_/_MOSI_/_PCINT2)_PB2_16") (pintype "passive"))
    )
    (net (code "23") (name "/16U2_PB4") (class "Default")
      (node (ref "JP2") (pin "1") (pinfunction "1_1") (pintype "passive"))
      (node (ref "JP3") (pin "2") (pinfunction "2_2") (pintype "passive"))
      (node (ref "U2") (pin "18") (pinfunction "(T1_/_PCINT4)_PB4_18") (pintype "passive"))
    )
    (net (code "24") (name "/16U2_PROG_RST") (class "Default")
      (node (ref "JP1") (pin "2") (pinfunction "2_2") (pintype "passive"))
      (node (ref "R1") (pin "1") (pinfunction "1_1") (pintype "passive"))
      (node (ref "U2") (pin "13") (pinfunction "~{HW}B_/_AIN6_/_T0_/_INT7)_PD7_13") (pintype "passive"))
    )
    (net (code "25") (name "/16U2_RESET") (class "Default")
      (node (ref "JP3") (pin "4") (pinfunction "4_4") (pintype "passive"))
      (node (ref "R4") (pin "1") (pinfunction "1_1") (pintype "passive"))
      (node (ref "U2") (pin "24") (pinfunction "~{Rese}t_(PC1_/_dW)_24") (pintype "passive"))
      (node (ref "U5") (pin "4") (pinfunction "4_4") (pintype "passive"))
    )
    (net (code "26") (name "/328P_16MHz_XTAL1") (class "Default")
      (node (ref "C27") (pin "2") (pinfunction "2_2") (pintype "passive"))
      (node (ref "R16") (pin "1") (pinfunction "1_1") (pintype "passive"))
      (node (ref "U1") (pin "9") (pinfunction "PB6_(PCINT6/XTAL1/TOSC1)_9") (pintype "passive"))
      (node (ref "Y1") (pin "1") (pinfunction "1_1") (pintype "passive"))
    )
    (net (code "27") (name "/328P_16MHz_XTAL2") (class "Default")
      (node (ref "C25") (pin "2") (pinfunction "2_2") (pintype "passive"))
      (node (ref "R16") (pin "2") (pinfunction "2_2") (pintype "passive"))
      (node (ref "U1") (pin "10") (pinfunction "PB7_(PCINT7/XTAL2/TOSC2)_10") (pintype "passive"))
      (node (ref "Y1") (pin "2") (pinfunction "2_2") (pintype "passive"))
    )
    (net (code "28") (name "/328P_AUTO_RSTn") (class "Default")
      (node (ref "C11") (pin "1") (pinfunction "1_1") (pintype "passive"))
      (node (ref "R18") (pin "1") (pinfunction "1_1") (pintype "passive"))
      (node (ref "U6") (pin "1") (pinfunction "1_1") (pintype "passive"))
    )
    (net (code "29") (name "/328P_BUF_RSTn") (class "Default")
      (node (ref "C32") (pin "2") (pinfunction "2_2") (pintype "passive"))
      (node (ref "R24") (pin "2") (pinfunction "2_2") (pintype "passive"))
      (node (ref "U6") (pin "2") (pinfunction "2_2") (pintype "passive"))
    )
    (net (code "30") (name "/328P_RESET") (class "Default")
      (node (ref "J1") (pin "3") (pinfunction "3_3") (pintype "passive"))
      (node (ref "J5") (pin "5") (pinfunction "5_5") (pintype "passive"))
      (node (ref "JP3") (pin "1") (pinfunction "1_1") (pintype "passive"))
      (node (ref "R14") (pin "1") (pinfunction "1_1") (pintype "passive"))
      (node (ref "U1") (pin "1") (pinfunction "PC6_(PCINT14~{/RESE}T)_1") (pintype "passive"))
      (node (ref "U6") (pin "4") (pinfunction "4_4") (pintype "passive"))
    )
    (net (code "31") (name "/AD0") (class "Default")
      (node (ref "J2") (pin "1") (pinfunction "1_1") (pintype "passive"))
      (node (ref "U1") (pin "23") (pinfunction "(ADC0/PCINT8)_PC0_23") (pintype "passive"))
    )
    (net (code "32") (name "/AD1") (class "Default")
      (node (ref "J2") (pin "2") (pinfunction "2_2") (pintype "passive"))
      (node (ref "U1") (pin "24") (pinfunction "(ADC1/PCINT9)_PC1_24") (pintype "passive"))
    )
    (net (code "33") (name "/AD2") (class "Default")
      (node (ref "J2") (pin "3") (pinfunction "3_3") (pintype "passive"))
      (node (ref "U1") (pin "25") (pinfunction "(ADC2/PCINT10)_PC2_25") (pintype "passive"))
    )
    (net (code "34") (name "/AD3") (class "Default")
      (node (ref "J2") (pin "4") (pinfunction "4_4") (pintype "passive"))
      (node (ref "U1") (pin "26") (pinfunction "(ADC3/PCINT11)_PC3_26") (pintype "passive"))
    )
    (net (code "35") (name "/AD4{slash}SDA") (class "Default")
      (node (ref "J2") (pin "5") (pinfunction "5_5") (pintype "passive"))
      (node (ref "J4") (pin "9") (pinfunction "9_9") (pintype "passive"))
      (node (ref "U1") (pin "27") (pinfunction "(ADC4/SDA/PCINT12)_PC4_27") (pintype "passive"))
    )
    (net (code "36") (name "/AD5{slash}SCL") (class "Default")
      (node (ref "J2") (pin "6") (pinfunction "6_6") (pintype "passive"))
      (node (ref "J4") (pin "10") (pinfunction "10_10") (pintype "passive"))
      (node (ref "U1") (pin "28") (pinfunction "(ADC5/SCL/PCINT13)_PC5_28") (pintype "passive"))
    )
    (net (code "37") (name "/BTN_RSTn") (class "Default")
      (node (ref "D6") (pin "2") (pinfunction "An_2") (pintype "passive"))
      (node (ref "R20") (pin "1") (pinfunction "1_1") (pintype "passive"))
      (node (ref "R24") (pin "1") (pinfunction "1_1") (pintype "passive"))
      (node (ref "SW1") (pin "1") (pinfunction "1_1") (pintype "passive"))
      (node (ref "SW1") (pin "2") (pinfunction "2_2") (pintype "passive"))
    )
    (net (code "38") (name "/CON_USB_N") (class "Default")
      (node (ref "J7") (pin "2") (pinfunction "2_2") (pintype "passive"))
      (node (ref "R6") (pin "1") (pinfunction "1_1") (pintype "passive"))
      (node (ref "Z2") (pin "2") (pinfunction "2_2") (pintype "passive"))
    )
    (net (code "39") (name "/CON_USB_P") (class "Default")
      (node (ref "J7") (pin "3") (pinfunction "3_3") (pintype "passive"))
      (node (ref "R7") (pin "1") (pinfunction "1_1") (pintype "passive"))
      (node (ref "Z1") (pin "2") (pinfunction "2_2") (pintype "passive"))
    )
    (net (code "40") (name "/IO0") (class "Default")
      (node (ref "J3") (pin "1") (pinfunction "1_1") (pintype "passive"))
      (node (ref "R10") (pin "2") (pinfunction "2_2") (pintype "passive"))
      (node (ref "U1") (pin "2") (pinfunction "(PCINT16/RXD)_PD0_2") (pintype "passive"))
    )
    (net (code "41") (name "/IO1") (class "Default")
      (node (ref "J3") (pin "2") (pinfunction "2_2") (pintype "passive"))
      (node (ref "R11") (pin "2") (pinfunction "2_2") (pintype "passive"))
      (node (ref "U1") (pin "3") (pinfunction "(PCINT17/TXD)_PD1_3") (pintype "passive"))
    )
    (net (code "42") (name "/IO2") (class "Default")
      (node (ref "J3") (pin "3") (pinfunction "3_3") (pintype "passive"))
      (node (ref "U1") (pin "4") (pinfunction "(PCINT18/INT0)_PD2_4") (pintype "passive"))
    )
    (net (code "43") (name "/IO3") (class "Default")
      (node (ref "J3") (pin "4") (pinfunction "4_4") (pintype "passive"))
      (node (ref "U1") (pin "5") (pinfunction "(PCINT19/OC2B/INT1)_PD3_5") (pintype "passive"))
    )
    (net (code "44") (name "/IO4") (class "Default")
      (node (ref "J3") (pin "5") (pinfunction "5_5") (pintype "passive"))
      (node (ref "U1") (pin "6") (pinfunction "(PCINT20/XCK/T0)_PD4_6") (pintype "passive"))
    )
    (net (code "45") (name "/IO5") (class "Default")
      (node (ref "J3") (pin "6") (pinfunction "6_6") (pintype "passive"))
      (node (ref "U1") (pin "11") (pinfunction "(PCINT21/OC0B/T1)_PD5_11") (pintype "passive"))
    )
    (net (code "46") (name "/IO6") (class "Default")
      (node (ref "J3") (pin "7") (pinfunction "7_7") (pintype "passive"))
      (node (ref "U1") (pin "12") (pinfunction "(PCINT22/OC0A/AIN0)_PD6_12") (pintype "passive"))
    )
    (net (code "47") (name "/IO7") (class "Default")
      (node (ref "J3") (pin "8") (pinfunction "8_8") (pintype "passive"))
      (node (ref "U1") (pin "13") (pinfunction "(PCINT23/AIN1)_PD7_13") (pintype "passive"))
    )
    (net (code "48") (name "/IO8") (class "Default")
      (node (ref "J4") (pin "1") (pinfunction "1_1") (pintype "passive"))
      (node (ref "R22") (pin "2") (pinfunction "2_2") (pintype "passive"))
      (node (ref "U1") (pin "14") (pinfunction "(PCINT0/CLKO/ICP1)_PB0_14") (pintype "passive"))
    )
    (net (code "49") (name "/IO9") (class "Default")
      (node (ref "J4") (pin "2") (pinfunction "2_2") (pintype "passive"))
      (node (ref "U1") (pin "15") (pinfunction "(OC1A/PCINT1)_PB1_15") (pintype "passive"))
    )
    (net (code "50") (name "/MISO") (class "Default")
      (node (ref "J4") (pin "5") (pinfunction "5_5") (pintype "passive"))
      (node (ref "J5") (pin "1") (pinfunction "1_1") (pintype "passive"))
      (node (ref "U1") (pin "18") (pinfunction "(MISO/PCINT4)_PB4_18") (pintype "passive"))
    )
    (net (code "51") (name "/MOSI") (class "Default")
      (node (ref "J4") (pin "4") (pinfunction "4_4") (pintype "passive"))
      (node (ref "J5") (pin "4") (pinfunction "4_4") (pintype "passive"))
      (node (ref "U1") (pin "17") (pinfunction "(MOSI/OC2A/PCINT3)_PB3_17") (pintype "passive"))
    )
    (net (code "52") (name "/SCK") (class "Default")
      (node (ref "J4") (pin "6") (pinfunction "6_6") (pintype "passive"))
      (node (ref "J5") (pin "3") (pinfunction "3_3") (pintype "passive"))
      (node (ref "R13") (pin "2") (pinfunction "2_2") (pintype "passive"))
      (node (ref "U4") (pin "1") (pinfunction "1_1") (pintype "passive"))
      (node (ref "U4") (pin "2") (pinfunction "2_2") (pintype "passive"))
    )
    (net (code "53") (name "/SCK_R") (class "Default")
      (node (ref "R13") (pin "1") (pinfunction "1_1") (pintype "passive"))
      (node (ref "U1") (pin "19") (pinfunction "(SCK/PCINT5)_PB5_19") (pintype "passive"))
    )
    (net (code "54") (name "/SS") (class "Default")
      (node (ref "J4") (pin "3") (pinfunction "3_3") (pintype "passive"))
      (node (ref "U1") (pin "16") (pinfunction "(SS/OC1B/PCINT2)_PB2_16") (pintype "passive"))
    )
    (net (code "55") (name "/USB_N") (class "Default")
      (node (ref "R6") (pin "2") (pinfunction "2_2") (pintype "passive"))
      (node (ref "U2") (pin "30") (pinfunction "D-_30") (pintype "passive"))
    )
    (net (code "56") (name "/USB_P") (class "Default")
      (node (ref "R7") (pin "2") (pinfunction "2_2") (pintype "passive"))
      (node (ref "U2") (pin "29") (pinfunction "D+_29") (pintype "passive"))
    )
    (net (code "57") (name "/USER_BUTTON") (class "Default")
      (node (ref "R21") (pin "1") (pinfunction "1_1") (pintype "passive"))
      (node (ref "R25") (pin "1") (pinfunction "1_1") (pintype "passive"))
      (node (ref "SW2") (pin "1") (pinfunction "1_1") (pintype "passive"))
      (node (ref "SW2") (pin "2") (pinfunction "2_2") (pintype "passive"))
    )
    (net (code "58") (name "/USER_BUTTON_BUFF") (class "Default")
      (node (ref "C33") (pin "2") (pinfunction "2_2") (pintype "passive"))
      (node (ref "R25") (pin "2") (pinfunction "2_2") (pintype "passive"))
      (node (ref "U7") (pin "1") (pinfunction "1_1") (pintype "passive"))
      (node (ref "U7") (pin "2") (pinfunction "2_2") (pintype "passive"))
    )
    (net (code "59") (name "GND") (class "Default")
      (node (ref "C1") (pin "2") (pinfunction "2_2") (pintype "passive"))
      (node (ref "C10") (pin "1") (pinfunction "1_1") (pintype "passive"))
      (node (ref "C12") (pin "1") (pinfunction "1_1") (pintype "passive"))
      (node (ref "C13") (pin "1") (pinfunction "1_1") (pintype "passive"))
      (node (ref "C14") (pin "1") (pinfunction "1_1") (pintype "passive"))
      (node (ref "C15") (pin "1") (pinfunction "1_1") (pintype "passive"))
      (node (ref "C16") (pin "1") (pinfunction "1_1") (pintype "passive"))
      (node (ref "C17") (pin "1") (pinfunction "1_1") (pintype "passive"))
      (node (ref "C19") (pin "1") (pinfunction "1_1") (pintype "passive"))
      (node (ref "C2") (pin "2") (pinfunction "2_2") (pintype "passive"))
      (node (ref "C20") (pin "1") (pinfunction "1_1") (pintype "passive"))
      (node (ref "C21") (pin "1") (pinfunction "1_1") (pintype "passive"))
      (node (ref "C22") (pin "1") (pinfunction "1_1") (pintype "passive"))
      (node (ref "C23") (pin "1") (pinfunction "1_1") (pintype "passive"))
      (node (ref "C24") (pin "1") (pinfunction "1_1") (pintype "passive"))
      (node (ref "C25") (pin "1") (pinfunction "1_1") (pintype "passive"))
      (node (ref "C26") (pin "1") (pinfunction "1_1") (pintype "passive"))
      (node (ref "C27") (pin "1") (pinfunction "1_1") (pintype "passive"))
      (node (ref "C28") (pin "1") (pinfunction "1_1") (pintype "passive"))
      (node (ref "C29") (pin "1") (pinfunction "1_1") (pintype "passive"))
      (node (ref "C3") (pin "1") (pinfunction "1_1") (pintype "passive"))
      (node (ref "C30") (pin "1") (pinfunction "1_1") (pintype "passive"))
      (node (ref "C31") (pin "1") (pinfunction "1_1") (pintype "passive"))
      (node (ref "C32") (pin "1") (pinfunction "1_1") (pintype "passive"))
      (node (ref "C33") (pin "1") (pinfunction "1_1") (pintype "passive"))
      (node (ref "C34") (pin "1") (pinfunction "1_1") (pintype "passive"))
      (node (ref "C4") (pin "1") (pinfunction "1_1") (pintype "passive"))
      (node (ref "C5") (pin "1") (pinfunction "1_1") (pintype "passive"))
      (node (ref "C6") (pin "1") (pinfunction "1_1") (pintype "passive"))
      (node (ref "C7") (pin "1") (pinfunction "1_1") (pintype "passive"))
      (node (ref "C8") (pin "1") (pinfunction "1_1") (pintype "passive"))
      (node (ref "C9") (pin "1") (pinfunction "1_1") (pintype "passive"))
      (node (ref "D1") (pin "1") (pinfunction "Ca_1") (pintype "passive"))
      (node (ref "J1") (pin "6") (pinfunction "6_6") (pintype "passive"))
      (node (ref "J1") (pin "7") (pinfunction "7_7") (pintype "passive"))
      (node (ref "J4") (pin "7") (pinfunction "7_7") (pintype "passive"))
      (node (ref "J5") (pin "6") (pinfunction "6_6") (pintype "passive"))
      (node (ref "J6") (pin "6") (pinfunction "6_6") (pintype "passive"))
      (node (ref "J7") (pin "10") (pinfunction "10_10") (pintype "passive"))
      (node (ref "J7") (pin "11") (pinfunction "11_11") (pintype "passive"))
      (node (ref "J7") (pin "5") (pinfunction "5_5") (pintype "passive"))
      (node (ref "J7") (pin "6") (pinfunction "6_6") (pintype "passive"))
      (node (ref "J7") (pin "7") (pinfunction "7_7") (pintype "passive"))
      (node (ref "J7") (pin "8") (pinfunction "8_8") (pintype "passive"))
      (node (ref "J7") (pin "9") (pinfunction "9_9") (pintype "passive"))
      (node (ref "J9") (pin "1") (pinfunction "1_1") (pintype "passive"))
      (node (ref "MH1") (pin "1") (pinfunction "1_1") (pintype "passive"))
      (node (ref "MH2") (pin "1") (pinfunction "1_1") (pintype "passive"))
      (node (ref "MH3") (pin "1") (pinfunction "1_1") (pintype "passive"))
      (node (ref "R12") (pin "1") (pinfunction "1_1") (pintype "passive"))
      (node (ref "R8") (pin "2") (pinfunction "2_2") (pintype "passive"))
      (node (ref "SW1") (pin "3") (pinfunction "3_3") (pintype "passive"))
      (node (ref "SW1") (pin "4") (pinfunction "4_4") (pintype "passive"))
      (node (ref "SW2") (pin "3") (pinfunction "3_3") (pintype "passive"))
      (node (ref "SW2") (pin "4") (pinfunction "4_4") (pintype "passive"))
      (node (ref "U1") (pin "22") (pinfunction "GND_2_22") (pintype "passive"))
      (node (ref "U1") (pin "8") (pinfunction "GND_1_8") (pintype "passive"))
      (node (ref "U2") (pin "28") (pinfunction "UGND_28") (pintype "passive"))
      (node (ref "U2") (pin "3") (pinfunction "GND_3") (pintype "passive"))
      (node (ref "U3") (pin "3") (pinfunction "GND_3") (pintype "passive"))
      (node (ref "U3") (pin "6") (pinfunction "EPAD_6") (pintype "passive"))
      (node (ref "U4") (pin "3") (pinfunction "3_3") (pintype "passive"))
      (node (ref "U5") (pin "3") (pinfunction "3_3") (pintype "passive"))
      (node (ref "U6") (pin "3") (pinfunction "3_3") (pintype "passive"))
      (node (ref "U7") (pin "3") (pinfunction "3_3") (pintype "passive"))
      (node (ref "Z1") (pin "1") (pinfunction "1_1") (pintype "passive"))
      (node (ref "Z2") (pin "1") (pinfunction "1_1") (pintype "passive"))
    )
    (net (code "60") (name "Net-(C11-Pad2)") (class "Default")
      (node (ref "C11") (pin "2") (pinfunction "2_2") (pintype "passive"))
      (node (ref "JP1") (pin "1") (pinfunction "1_1") (pintype "passive"))
    )
    (net (code "61") (name "Net-(D1-An)") (class "Default")
      (node (ref "D1") (pin "2") (pinfunction "An_2") (pintype "passive"))
      (node (ref "R17") (pin "1") (pinfunction "1_1") (pintype "passive"))
    )
    (net (code "62") (name "Net-(D2-An)") (class "Default")
      (node (ref "D2") (pin "2") (pinfunction "An_2") (pintype "passive"))
      (node (ref "R15") (pin "1") (pinfunction "1_1") (pintype "passive"))
    )
    (net (code "63") (name "Net-(D2-Ca)") (class "Default")
      (node (ref "D2") (pin "1") (pinfunction "Ca_1") (pintype "passive"))
      (node (ref "U4") (pin "4") (pinfunction "4_4") (pintype "passive"))
    )
    (net (code "64") (name "Net-(D3-An)") (class "Default")
      (node (ref "D3") (pin "2") (pinfunction "An_2") (pintype "passive"))
      (node (ref "R2") (pin "1") (pinfunction "1_1") (pintype "passive"))
    )
    (net (code "65") (name "Net-(D4-An)") (class "Default")
      (node (ref "D4") (pin "2") (pinfunction "An_2") (pintype "passive"))
      (node (ref "R3") (pin "1") (pinfunction "1_1") (pintype "passive"))
    )
    (net (code "66") (name "Net-(D5-An)") (class "Default")
      (node (ref "D5") (pin "2") (pinfunction "An_2") (pintype "passive"))
      (node (ref "R19") (pin "1") (pinfunction "1_1") (pintype "passive"))
      (node (ref "R23") (pin "1") (pinfunction "1_1") (pintype "passive"))
    )
    (net (code "67") (name "Net-(J7-Pad4)") (class "Default")
      (node (ref "J7") (pin "4") (pinfunction "4_4") (pintype "passive"))
      (node (ref "R8") (pin "1") (pinfunction "1_1") (pintype "passive"))
    )
    (net (code "68") (name "Net-(JP1-Pad3)") (class "Default")
      (node (ref "JP1") (pin "3") (pinfunction "3_3") (pintype "passive"))
      (node (ref "R12") (pin "2") (pinfunction "2_2") (pintype "passive"))
    )
    (net (code "69") (name "Net-(R22-Pad1)") (class "Default")
      (node (ref "R22") (pin "1") (pinfunction "1_1") (pintype "passive"))
      (node (ref "U7") (pin "4") (pinfunction "4_4") (pintype "passive"))
    )
    (net (code "70") (name "Net-(U2-XTAL1)") (class "Default")
      (node (ref "C10") (pin "2") (pinfunction "2_2") (pintype "passive"))
      (node (ref "R9") (pin "1") (pinfunction "1_1") (pintype "passive"))
      (node (ref "U2") (pin "1") (pinfunction "XTAL1_1") (pintype "passive"))
      (node (ref "Y2") (pin "1") (pinfunction "1_1") (pintype "passive"))
    )
    (net (code "71") (name "Net-(U2-XTAL2_{slash}_(PC0))") (class "Default")
      (node (ref "C9") (pin "2") (pinfunction "2_2") (pintype "passive"))
      (node (ref "R9") (pin "2") (pinfunction "2_2") (pintype "passive"))
      (node (ref "U2") (pin "2") (pinfunction "XTAL2_/_(PC0)_2") (pintype "passive"))
      (node (ref "Y2") (pin "2") (pinfunction "2_2") (pintype "passive"))
    )
    (net (code "72") (name "unconnected-(C6-Pad2)") (class "Default")
      (node (ref "C6") (pin "2") (pinfunction "2_2") (pintype "passive"))
    )
    (net (code "73") (name "unconnected-(C14-Pad2)") (class "Default")
      (node (ref "C14") (pin "2") (pinfunction "2_2") (pintype "passive"))
    )
    (net (code "74") (name "unconnected-(C19-Pad2)") (class "Default")
      (node (ref "C19") (pin "2") (pinfunction "2_2") (pintype "passive"))
    )
    (net (code "75") (name "unconnected-(C20-Pad2)") (class "Default")
      (node (ref "C20") (pin "2") (pinfunction "2_2") (pintype "passive"))
    )
    (net (code "76") (name "unconnected-(J1-Pad1)") (class "Default")
      (node (ref "J1") (pin "1") (pinfunction "1_1") (pintype "passive+no_connect"))
    )
    (net (code "77") (name "unconnected-(J1-Pad8)") (class "Default")
      (node (ref "J1") (pin "8") (pinfunction "8_8") (pintype "passive+no_connect"))
    )
    (net (code "78") (name "unconnected-(MH4-Pad1)") (class "Default")
      (node (ref "MH4") (pin "1") (pinfunction "1_1") (pintype "passive+no_connect"))
    )
    (net (code "79") (name "unconnected-(U2-(AIN0_{slash}_INT1)_PD1-Pad7)") (class "Default")
      (node (ref "U2") (pin "7") (pinfunction "(AIN0_/_INT1)_PD1_7") (pintype "passive+no_connect"))
    )
    (net (code "80") (name "unconnected-(U2-(INT4_{slash}_ICP1_{slash}_CLKO)_PC7-Pad22)") (class "Default")
      (node (ref "U2") (pin "22") (pinfunction "(INT4_/_ICP1_/_CLKO)_PC7_22") (pintype "passive+no_connect"))
    )
    (net (code "81") (name "unconnected-(U2-(OC.0B_{slash}_INT0)_PD0-Pad6)") (class "Default")
      (node (ref "U2") (pin "6") (pinfunction "(OC.0B_/_INT0)_PD0_6") (pintype "passive+no_connect"))
    )
    (net (code "82") (name "unconnected-(U2-(OC.1A_{slash}_PCINT8)_PC6-Pad23)") (class "Default")
      (node (ref "U2") (pin "23") (pinfunction "(OC.1A_/_PCINT8)_PC6_23") (pintype "passive+no_connect"))
    )
    (net (code "83") (name "unconnected-(U2-(PCINT10)_PC4-Pad26)") (class "Default")
      (node (ref "U2") (pin "26") (pinfunction "(PCINT10)_PC4_26") (pintype "passive+no_connect"))
    )
    (net (code "84") (name "unconnected-(U2-(PCINT11_{slash}AIN2_)_PC2-Pad5)") (class "Default")
      (node (ref "U2") (pin "5") (pinfunction "(PCINT11_/AIN2_)_PC2_5") (pintype "passive+no_connect"))
    )
    (net (code "85") (name "unconnected-(U2-UVCC-Pad31)") (class "Default")
      (node (ref "U2") (pin "31") (pinfunction "UVCC_31") (pintype "passive"))
    )
    (net (code "86") (name "unconnected-(U2-_(_PCINT9{slash}_OC.1B)_PC5-Pad25)") (class "Default")
      (node (ref "U2") (pin "25") (pinfunction "_(_PCINT9/_OC.1B)_PC5_25") (pintype "passive+no_connect"))
    )
    (net (code "87") (name "unconnected-(U2-~{(RT}S_{slash}_AIN5_{slash}_INT6)_PD6-Pad12)") (class "Default")
      (node (ref "U2") (pin "12") (pinfunction "~{(RT}S_/_AIN5_/_INT6)_PD6_12") (pintype "passive+no_connect"))
    )
    (net (code "88") (name "unconnected-(U2-~{(S}S_{slash}_PCINT0)_PB0-Pad14)") (class "Default")
      (node (ref "U2") (pin "14") (pinfunction "~{(S}S_/_PCINT0)_PB0_14") (pintype "passive+no_connect"))
    )
  )
)
